# controller-board.net
KiCad netlist of a schematic drawn in EAGLE
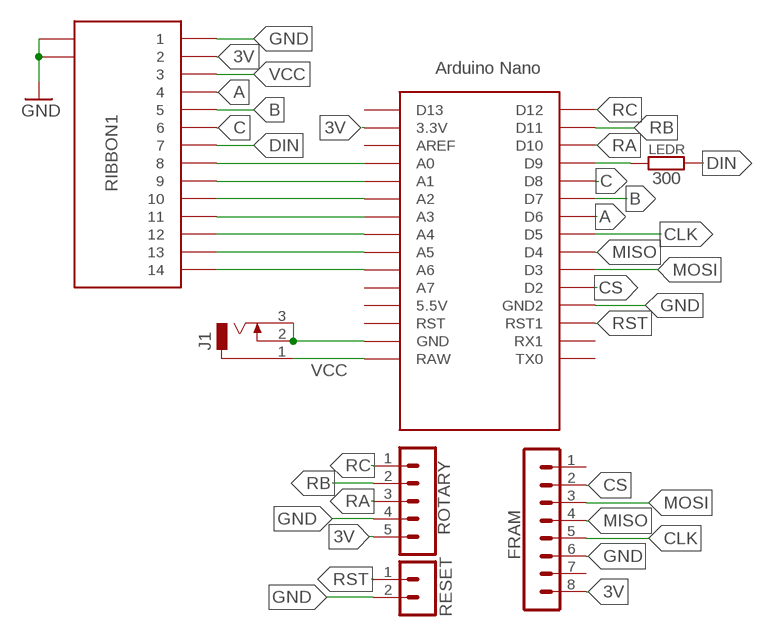
[diagram p0: schematic, sheet 1]

(export (version "E")
  (design (tool "Eeschema 10.0.6"))
  (components
    (comp (ref "FRAM")
      (value "MB85RS2MTA")
      (footprint "eagle-import:MA08-1")
      (libsource (lib "eagle-import") (part "MA08-1"))
    )
    (comp (ref "J1")
      (value "DCJ0202")
      (footprint "eagle-import:DCJ0202")
      (libsource (lib "eagle-import") (part "DCJ0202"))
    )
    (comp (ref "LEDR")
      (value "300")
      (footprint "eagle-import:0207_10")
      (libsource (lib "eagle-import") (part "R-EU_0207/10"))
    )
    (comp (ref "RESET")
      (value "B2B-PH-K")
      (footprint "eagle-import:B2B-PH-K")
      (libsource (lib "eagle-import") (part "B2B-PH-K"))
    )
    (comp (ref "RIBBON1")
      (value "686114148922")
      (footprint "eagle-import:686114148922")
      (fields (field (name "MOUSER_PART_NUMBER") "710-686114148922"))
      (libsource (lib "eagle-import") (part "686114148922"))
    )
    (comp (ref "ROTARY")
      (value "B5B-PH-K")
      (footprint "eagle-import:B5B-PH-K")
      (libsource (lib "eagle-import") (part "B5B-PH-K"))
    )
    (comp (ref "U$1")
      (value "NANO")
      (footprint "eagle-import:NANO")
      (libsource (lib "eagle-import") (part "NANO"))
    )
  )
  (nets
    (net (code "1") (name "3V") (class "Default")
      (node (ref "FRAM") (pin "8") (pinfunction "8_8") (pintype "passive"))
      (node (ref "RIBBON1") (pin "2") (pinfunction "2_2") (pintype "bidirectional"))
      (node (ref "ROTARY") (pin "5") (pinfunction "5_5") (pintype "passive"))
      (node (ref "U$1") (pin "3.3V") (pinfunction "3.3V_3.3V") (pintype "bidirectional"))
    )
    (net (code "2") (name "A") (class "Default")
      (node (ref "RIBBON1") (pin "4") (pinfunction "4_4") (pintype "bidirectional"))
      (node (ref "U$1") (pin "D6") (pinfunction "D6_D6") (pintype "bidirectional"))
    )
    (net (code "3") (name "B") (class "Default")
      (node (ref "RIBBON1") (pin "5") (pinfunction "5_5") (pintype "bidirectional"))
      (node (ref "U$1") (pin "D7") (pinfunction "D7_D7") (pintype "bidirectional"))
    )
    (net (code "4") (name "C") (class "Default")
      (node (ref "RIBBON1") (pin "6") (pinfunction "6_6") (pintype "bidirectional"))
      (node (ref "U$1") (pin "D8") (pinfunction "D8_D8") (pintype "bidirectional"))
    )
    (net (code "5") (name "CLK") (class "Default")
      (node (ref "FRAM") (pin "5") (pinfunction "5_5") (pintype "passive"))
      (node (ref "U$1") (pin "D5") (pinfunction "D5_D5") (pintype "bidirectional"))
    )
    (net (code "6") (name "CS") (class "Default")
      (node (ref "FRAM") (pin "2") (pinfunction "2_2") (pintype "passive"))
      (node (ref "U$1") (pin "D2") (pinfunction "D2_D2") (pintype "bidirectional"))
    )
    (net (code "7") (name "DIN") (class "Default")
      (node (ref "LEDR") (pin "2") (pinfunction "2_2") (pintype "passive"))
      (node (ref "RIBBON1") (pin "7") (pinfunction "7_7") (pintype "bidirectional"))
    )
    (net (code "8") (name "GND") (class "Default")
      (node (ref "FRAM") (pin "6") (pinfunction "6_6") (pintype "passive"))
      (node (ref "J1") (pin "2") (pinfunction "2_2") (pintype "passive"))
      (node (ref "J1") (pin "3") (pinfunction "3_3") (pintype "passive"))
      (node (ref "RESET") (pin "2") (pinfunction "2_2") (pintype "passive"))
      (node (ref "RIBBON1") (pin "1") (pinfunction "1_1") (pintype "bidirectional"))
      (node (ref "RIBBON1") (pin "MP1") (pinfunction "MP1_MP1") (pintype "bidirectional"))
      (node (ref "RIBBON1") (pin "MP2") (pinfunction "MP2_MP2") (pintype "bidirectional"))
      (node (ref "ROTARY") (pin "4") (pinfunction "4_4") (pintype "passive"))
      (node (ref "U$1") (pin "GND") (pinfunction "GND_GND") (pintype "bidirectional"))
      (node (ref "U$1") (pin "GND1") (pinfunction "GND2_GND1") (pintype "bidirectional"))
    )
    (net (code "9") (name "MISO") (class "Default")
      (node (ref "FRAM") (pin "4") (pinfunction "4_4") (pintype "passive"))
      (node (ref "U$1") (pin "D4") (pinfunction "D4_D4") (pintype "bidirectional"))
    )
    (net (code "10") (name "MOSI") (class "Default")
      (node (ref "FRAM") (pin "3") (pinfunction "3_3") (pintype "passive"))
      (node (ref "U$1") (pin "D3") (pinfunction "D3_D3") (pintype "bidirectional"))
    )
    (net (code "11") (name "Net-(LEDR-Pad1)") (class "Default")
      (node (ref "LEDR") (pin "1") (pinfunction "1_1") (pintype "passive"))
      (node (ref "U$1") (pin "D9") (pinfunction "D9_D9") (pintype "bidirectional"))
    )
    (net (code "12") (name "Net-(RIBBON1-Pad8)") (class "Default")
      (node (ref "RIBBON1") (pin "8") (pinfunction "8_8") (pintype "bidirectional"))
      (node (ref "U$1") (pin "A0") (pinfunction "A0_A0") (pintype "bidirectional"))
    )
    (net (code "13") (name "Net-(RIBBON1-Pad9)") (class "Default")
      (node (ref "RIBBON1") (pin "9") (pinfunction "9_9") (pintype "bidirectional"))
      (node (ref "U$1") (pin "A1") (pinfunction "A1_A1") (pintype "bidirectional"))
    )
    (net (code "14") (name "Net-(RIBBON1-Pad10)") (class "Default")
      (node (ref "RIBBON1") (pin "10") (pinfunction "10_10") (pintype "bidirectional"))
      (node (ref "U$1") (pin "A2") (pinfunction "A2_A2") (pintype "bidirectional"))
    )
    (net (code "15") (name "Net-(RIBBON1-Pad11)") (class "Default")
      (node (ref "RIBBON1") (pin "11") (pinfunction "11_11") (pintype "bidirectional"))
      (node (ref "U$1") (pin "A3") (pinfunction "A3_A3") (pintype "bidirectional"))
    )
    (net (code "16") (name "Net-(RIBBON1-Pad12)") (class "Default")
      (node (ref "RIBBON1") (pin "12") (pinfunction "12_12") (pintype "bidirectional"))
      (node (ref "U$1") (pin "A4") (pinfunction "A4_A4") (pintype "bidirectional"))
    )
    (net (code "17") (name "Net-(RIBBON1-Pad13)") (class "Default")
      (node (ref "RIBBON1") (pin "13") (pinfunction "13_13") (pintype "bidirectional"))
      (node (ref "U$1") (pin "A5") (pinfunction "A5_A5") (pintype "bidirectional"))
    )
    (net (code "18") (name "Net-(RIBBON1-Pad14)") (class "Default")
      (node (ref "RIBBON1") (pin "14") (pinfunction "14_14") (pintype "bidirectional"))
      (node (ref "U$1") (pin "A6") (pinfunction "A6_A6") (pintype "bidirectional"))
    )
    (net (code "19") (name "RA") (class "Default")
      (node (ref "ROTARY") (pin "3") (pinfunction "3_3") (pintype "passive"))
      (node (ref "U$1") (pin "D10") (pinfunction "D10_D10") (pintype "bidirectional"))
    )
    (net (code "20") (name "RB") (class "Default")
      (node (ref "ROTARY") (pin "2") (pinfunction "2_2") (pintype "passive"))
      (node (ref "U$1") (pin "D11") (pinfunction "D11_D11") (pintype "bidirectional"))
    )
    (net (code "21") (name "RC") (class "Default")
      (node (ref "ROTARY") (pin "1") (pinfunction "1_1") (pintype "passive"))
      (node (ref "U$1") (pin "D12") (pinfunction "D12_D12") (pintype "bidirectional"))
    )
    (net (code "22") (name "RST") (class "Default")
      (node (ref "RESET") (pin "1") (pinfunction "1_1") (pintype "passive"))
      (node (ref "U$1") (pin "RST1") (pinfunction "RST1_RST1") (pintype "bidirectional"))
    )
    (net (code "23") (name "VCC") (class "Default")
      (node (ref "J1") (pin "1") (pinfunction "1_1") (pintype "passive"))
      (node (ref "RIBBON1") (pin "3") (pinfunction "3_3") (pintype "bidirectional"))
      (node (ref "U$1") (pin "RAW") (pinfunction "RAW_RAW") (pintype "bidirectional"))
    )
    (net (code "24") (name "unconnected-(FRAM-Pad1)") (class "Default")
      (node (ref "FRAM") (pin "1") (pinfunction "1_1") (pintype "passive"))
    )
    (net (code "25") (name "unconnected-(FRAM-Pad7)") (class "Default")
      (node (ref "FRAM") (pin "7") (pinfunction "7_7") (pintype "passive"))
    )
    (net (code "26") (name "unconnected-(U$1-5.5V-Pad5V)") (class "Default")
      (node (ref "U$1") (pin "5V") (pinfunction "5.5V_5V") (pintype "bidirectional"))
    )
    (net (code "27") (name "unconnected-(U$1-PadA7)") (class "Default")
      (node (ref "U$1") (pin "A7") (pinfunction "A7_A7") (pintype "bidirectional"))
    )
    (net (code "28") (name "unconnected-(U$1-PadAREF)") (class "Default")
      (node (ref "U$1") (pin "AREF") (pinfunction "AREF_AREF") (pintype "bidirectional"))
    )
    (net (code "29") (name "unconnected-(U$1-PadD13)") (class "Default")
      (node (ref "U$1") (pin "D13") (pinfunction "D13_D13") (pintype "bidirectional"))
    )
    (net (code "30") (name "unconnected-(U$1-PadICSP1)") (class "Default")
      (node (ref "U$1") (pin "ICSP1") (pinfunction "ICSP1_ICSP1") (pintype "bidirectional"))
    )
    (net (code "31") (name "unconnected-(U$1-PadICSP2)") (class "Default")
      (node (ref "U$1") (pin "ICSP2") (pinfunction "ICSP2_ICSP2") (pintype "bidirectional"))
    )
    (net (code "32") (name "unconnected-(U$1-PadICSP3)") (class "Default")
      (node (ref "U$1") (pin "ICSP3") (pinfunction "ICSP3_ICSP3") (pintype "bidirectional"))
    )
    (net (code "33") (name "unconnected-(U$1-PadICSP4)") (class "Default")
      (node (ref "U$1") (pin "ICSP4") (pinfunction "ICSP4_ICSP4") (pintype "bidirectional"))
    )
    (net (code "34") (name "unconnected-(U$1-PadICSP5)") (class "Default")
      (node (ref "U$1") (pin "ICSP5") (pinfunction "ICSP5_ICSP5") (pintype "bidirectional"))
    )
    (net (code "35") (name "unconnected-(U$1-PadICSP6)") (class "Default")
      (node (ref "U$1") (pin "ICSP6") (pinfunction "ICSP6_ICSP6") (pintype "bidirectional"))
    )
    (net (code "36") (name "unconnected-(U$1-PadRST)") (class "Default")
      (node (ref "U$1") (pin "RST") (pinfunction "RST_RST") (pintype "bidirectional"))
    )
    (net (code "37") (name "unconnected-(U$1-PadRX1)") (class "Default")
      (node (ref "U$1") (pin "RX1") (pinfunction "RX1_RX1") (pintype "bidirectional"))
    )
    (net (code "38") (name "unconnected-(U$1-PadTX0)") (class "Default")
      (node (ref "U$1") (pin "TX0") (pinfunction "TX0_TX0") (pintype "bidirectional"))
    )
  )
)
